# SaLFrostburn1_2.net
KiCad netlist of a schematic drawn in EAGLE
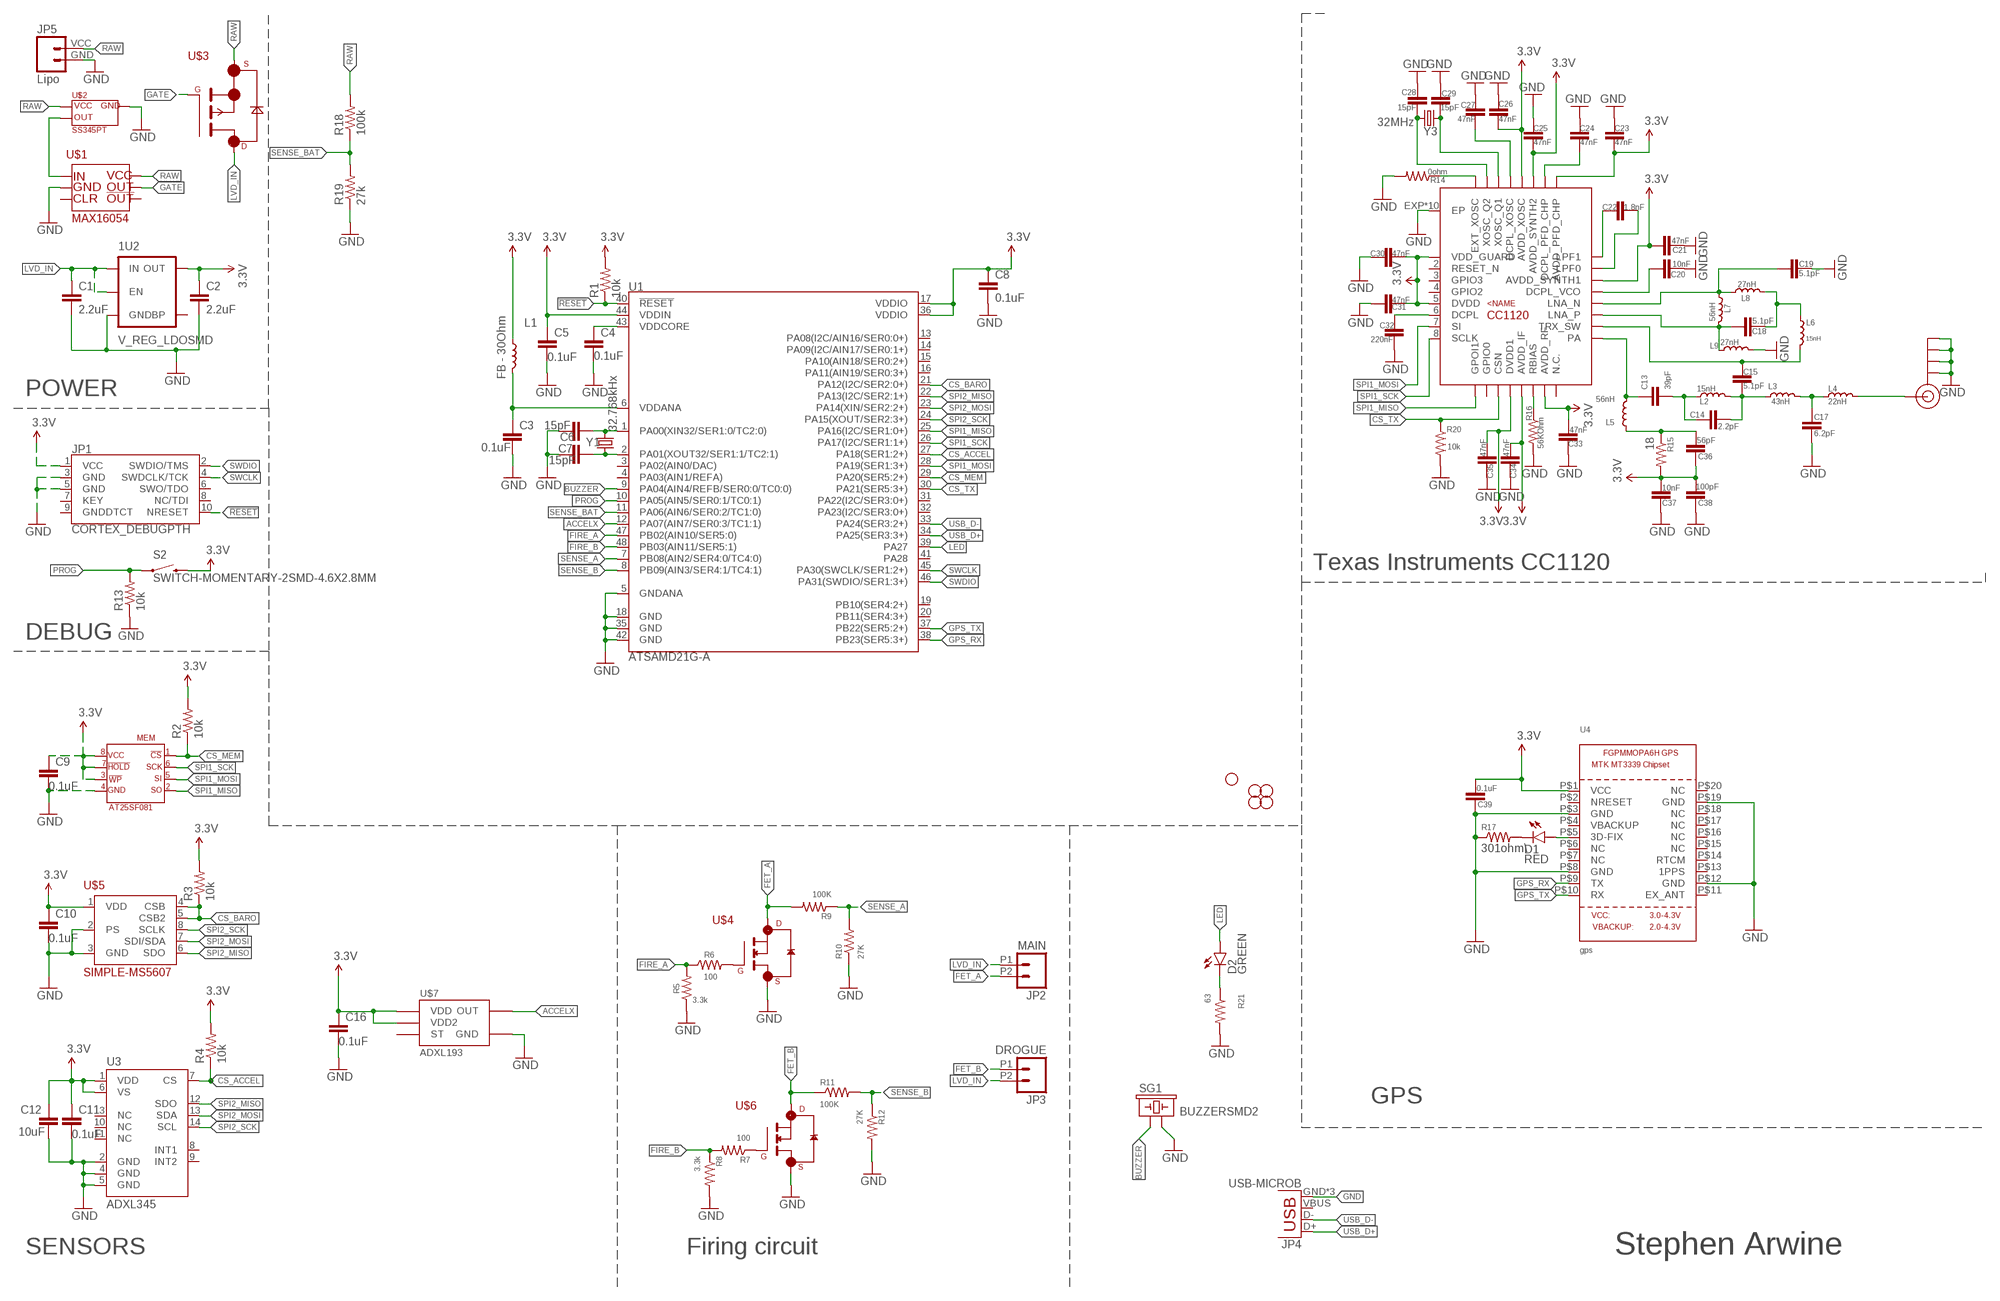
[diagram p0: schematic, sheet 1]

(export (version "E")
  (design (tool "Eeschema 10.0.6"))
  (components
    (comp (ref "1U2")
      (value "V_REG_LDOSMD")
      (footprint "eagle-import:SOT23-5")
      (libsource (lib "eagle-import") (part "V_REG_LDOSMD"))
    )
    (comp (ref "C1")
      (value "2.2uF")
      (footprint "eagle-import:0603-CAP")
      (libsource (lib "eagle-import") (part "CAP0603-CAP"))
    )
    (comp (ref "C2")
      (value "2.2uF")
      (footprint "eagle-import:0603-CAP")
      (libsource (lib "eagle-import") (part "CAP0603-CAP"))
    )
    (comp (ref "C3")
      (value "0.1uF")
      (footprint "eagle-import:0402-CAP")
      (libsource (lib "eagle-import") (part "SparkFun-Passives_CAP0402-CAP"))
    )
    (comp (ref "C4")
      (value "0.1uF")
      (footprint "eagle-import:0402-CAP")
      (libsource (lib "eagle-import") (part "SparkFun-Passives_CAP0402-CAP"))
    )
    (comp (ref "C5")
      (value "0.1uF")
      (footprint "eagle-import:0402-CAP")
      (libsource (lib "eagle-import") (part "SparkFun-Passives_CAP0402-CAP"))
    )
    (comp (ref "C6")
      (value "15pF")
      (footprint "eagle-import:0402-CAP")
      (libsource (lib "eagle-import") (part "SparkFun-Passives_CAP0402-CAP"))
    )
    (comp (ref "C7")
      (value "15pF")
      (footprint "eagle-import:0402-CAP")
      (libsource (lib "eagle-import") (part "SparkFun-Passives_CAP0402-CAP"))
    )
    (comp (ref "C8")
      (value "0.1uF")
      (footprint "eagle-import:0402-CAP")
      (libsource (lib "eagle-import") (part "SparkFun-Passives_CAP0402-CAP"))
    )
    (comp (ref "C9")
      (value "0.1uF")
      (footprint "eagle-import:0402-CAP")
      (libsource (lib "eagle-import") (part "SparkFun-Passives_CAP0402-CAP"))
    )
    (comp (ref "C10")
      (value "0.1uF")
      (footprint "eagle-import:0402-CAP")
      (libsource (lib "eagle-import") (part "SparkFun-Passives_CAP0402-CAP"))
    )
    (comp (ref "C11")
      (value "0.1uF")
      (footprint "eagle-import:0402-CAP")
      (libsource (lib "eagle-import") (part "SparkFun-Passives_CAP0402-CAP"))
    )
    (comp (ref "C12")
      (value "10uF")
      (footprint "eagle-import:0402-CAP")
      (libsource (lib "eagle-import") (part "SparkFun-Passives_CAP0402-CAP"))
    )
    (comp (ref "C13")
      (value "39pF")
      (footprint "eagle-import:0402-CAP")
      (libsource (lib "eagle-import") (part "CAP0402-CAP"))
    )
    (comp (ref "C14")
      (value "2.2pF")
      (footprint "eagle-import:0402-CAP")
      (libsource (lib "eagle-import") (part "CAP0402-CAP"))
    )
    (comp (ref "C15")
      (value "5.1pF")
      (footprint "eagle-import:0402-CAP")
      (libsource (lib "eagle-import") (part "CAP0402-CAP"))
    )
    (comp (ref "C16")
      (value "0.1uF")
      (footprint "eagle-import:0402-CAP")
      (libsource (lib "eagle-import") (part "SparkFun-Passives_CAP0402-CAP"))
    )
    (comp (ref "C17")
      (value "6.2pF")
      (footprint "eagle-import:0402-CAP")
      (libsource (lib "eagle-import") (part "CAP0402-CAP"))
    )
    (comp (ref "C18")
      (value "5.1pF")
      (footprint "eagle-import:0402-CAP")
      (libsource (lib "eagle-import") (part "CAP0402-CAP"))
    )
    (comp (ref "C19")
      (value "5.1pF")
      (footprint "eagle-import:0402-CAP")
      (libsource (lib "eagle-import") (part "CAP0402-CAP"))
    )
    (comp (ref "C20")
      (value "10nF")
      (footprint "eagle-import:0402-CAP")
      (libsource (lib "eagle-import") (part "CAP0402-CAP"))
    )
    (comp (ref "C21")
      (value "47nF")
      (footprint "eagle-import:0402-CAP")
      (libsource (lib "eagle-import") (part "CAP0402-CAP"))
    )
    (comp (ref "C22")
      (value "1.8nF")
      (footprint "eagle-import:0402-CAP")
      (libsource (lib "eagle-import") (part "CAP0402-CAP"))
    )
    (comp (ref "C23")
      (value "47nF")
      (footprint "eagle-import:0402-CAP")
      (libsource (lib "eagle-import") (part "CAP0402-CAP"))
    )
    (comp (ref "C24")
      (value "47nF")
      (footprint "eagle-import:0402-CAP")
      (libsource (lib "eagle-import") (part "CAP0402-CAP"))
    )
    (comp (ref "C25")
      (value "47nF")
      (footprint "eagle-import:0402-CAP")
      (libsource (lib "eagle-import") (part "CAP0402-CAP"))
    )
    (comp (ref "C26")
      (value "47nF")
      (footprint "eagle-import:0402-CAP")
      (libsource (lib "eagle-import") (part "CAP0402-CAP"))
    )
    (comp (ref "C27")
      (value "47nF")
      (footprint "eagle-import:0402-CAP")
      (libsource (lib "eagle-import") (part "CAP0402-CAP"))
    )
    (comp (ref "C28")
      (value "15pF")
      (footprint "eagle-import:0402-CAP")
      (libsource (lib "eagle-import") (part "CAP0402-CAP"))
    )
    (comp (ref "C29")
      (value "15pF")
      (footprint "eagle-import:0402-CAP")
      (libsource (lib "eagle-import") (part "CAP0402-CAP"))
    )
    (comp (ref "C30")
      (value "47nF")
      (footprint "eagle-import:0402-CAP")
      (libsource (lib "eagle-import") (part "CAP0402-CAP"))
    )
    (comp (ref "C31")
      (value "47nF")
      (footprint "eagle-import:0402-CAP")
      (libsource (lib "eagle-import") (part "CAP0402-CAP"))
    )
    (comp (ref "C32")
      (value "220nF")
      (footprint "eagle-import:0402-CAP")
      (libsource (lib "eagle-import") (part "CAP0402-CAP"))
    )
    (comp (ref "C33")
      (value "47nF")
      (footprint "eagle-import:0402-CAP")
      (libsource (lib "eagle-import") (part "CAP0402-CAP"))
    )
    (comp (ref "C34")
      (value "47nF")
      (footprint "eagle-import:0402-CAP")
      (libsource (lib "eagle-import") (part "CAP0402-CAP"))
    )
    (comp (ref "C35")
      (value "47nF")
      (footprint "eagle-import:0402-CAP")
      (libsource (lib "eagle-import") (part "CAP0402-CAP"))
    )
    (comp (ref "C36")
      (value "56pF")
      (footprint "eagle-import:0402-CAP")
      (libsource (lib "eagle-import") (part "CAP0402-CAP"))
    )
    (comp (ref "C37")
      (value "10nF")
      (footprint "eagle-import:0402-CAP")
      (libsource (lib "eagle-import") (part "CAP0402-CAP"))
    )
    (comp (ref "C38")
      (value "100pF")
      (footprint "eagle-import:0402-CAP")
      (libsource (lib "eagle-import") (part "CAP0402-CAP"))
    )
    (comp (ref "C39")
      (value "0.1uF")
      (footprint "eagle-import:0402-CAP")
      (libsource (lib "eagle-import") (part "CAP0402-CAP"))
    )
    (comp (ref "D1")
      (value "RED")
      (footprint "eagle-import:LED-0603")
      (libsource (lib "eagle-import") (part "LED-RED0603"))
    )
    (comp (ref "D2")
      (value "GREEN")
      (footprint "eagle-import:LED-1206")
      (libsource (lib "eagle-import") (part "LED-GREEN1206"))
    )
    (comp (ref "J$1")
      (value "SMA_EDGE")
      (footprint "eagle-import:SMA-EDGE")
      (libsource (lib "eagle-import") (part "SMA_EDGE"))
    )
    (comp (ref "JP1")
      (value "CORTEX_DEBUGPTH")
      (footprint "eagle-import:2X5-PTH-1.27MM")
      (libsource (lib "eagle-import") (part "CORTEX_DEBUGPTH"))
    )
    (comp (ref "JP2")
      (value "MAIN")
      (footprint "eagle-import:1X02_2.54_SCREWTERM")
      (libsource (lib "eagle-import") (part "M022.54MM_SCREWTERM"))
    )
    (comp (ref "JP3")
      (value "DROGUE")
      (footprint "eagle-import:1X02_2.54_SCREWTERM")
      (libsource (lib "eagle-import") (part "M022.54MM_SCREWTERM"))
    )
    (comp (ref "JP4")
      (value "USB-MICROB")
      (footprint "eagle-import:USB-MICROB")
      (libsource (lib "eagle-import") (part "USB-MICROB"))
    )
    (comp (ref "JP5")
      (value "Lipo")
      (footprint "eagle-import:JST-2-SMD-VERT")
      (libsource (lib "eagle-import") (part "M024UCON-15767"))
    )
    (comp (ref "L1")
      (value "FB - 30Ohm")
      (footprint "eagle-import:0603")
      (libsource (lib "eagle-import") (part "INDUCTOR0603"))
    )
    (comp (ref "L2")
      (value "15nH")
      (footprint "eagle-import:C0402")
      (libsource (lib "eagle-import") (part "INDUCTOR0402"))
    )
    (comp (ref "L3")
      (value "43nH")
      (footprint "eagle-import:C0402")
      (libsource (lib "eagle-import") (part "INDUCTOR0402"))
    )
    (comp (ref "L4")
      (value "22nH")
      (footprint "eagle-import:C0402")
      (libsource (lib "eagle-import") (part "INDUCTOR0402"))
    )
    (comp (ref "L5")
      (value "56nH")
      (footprint "eagle-import:C0402")
      (libsource (lib "eagle-import") (part "INDUCTOR0402"))
    )
    (comp (ref "L6")
      (value "15nH")
      (footprint "eagle-import:C0402")
      (libsource (lib "eagle-import") (part "INDUCTOR0402"))
    )
    (comp (ref "L7")
      (value "56nH")
      (footprint "eagle-import:C0402")
      (libsource (lib "eagle-import") (part "INDUCTOR0402"))
    )
    (comp (ref "L8")
      (value "27nH")
      (footprint "eagle-import:C0402")
      (libsource (lib "eagle-import") (part "INDUCTOR0402"))
    )
    (comp (ref "L9")
      (value "27nH")
      (footprint "eagle-import:C0402")
      (libsource (lib "eagle-import") (part "INDUCTOR0402"))
    )
    (comp (ref "MEM")
      (value "AT25SF081")
      (footprint "eagle-import:AT25SF081")
      (libsource (lib "eagle-import") (part "AT25SF081"))
    )
    (comp (ref "R1")
      (value "10k")
      (footprint "eagle-import:0402-RES")
      (libsource (lib "eagle-import") (part "RESISTOR0402-RES"))
    )
    (comp (ref "R2")
      (value "10k")
      (footprint "eagle-import:0402-RES")
      (libsource (lib "eagle-import") (part "RESISTOR0402-RES"))
    )
    (comp (ref "R3")
      (value "10k")
      (footprint "eagle-import:0402-RES")
      (libsource (lib "eagle-import") (part "RESISTOR0402-RES"))
    )
    (comp (ref "R4")
      (value "10k")
      (footprint "eagle-import:0402-RES")
      (libsource (lib "eagle-import") (part "RESISTOR0402-RES"))
    )
    (comp (ref "R5")
      (value "3.3k")
      (footprint "eagle-import:0402-RES")
      (libsource (lib "eagle-import") (part "RESISTOR0402"))
    )
    (comp (ref "R6")
      (value "100")
      (footprint "eagle-import:0402-RES")
      (libsource (lib "eagle-import") (part "RESISTOR0402"))
    )
    (comp (ref "R7")
      (value "100")
      (footprint "eagle-import:0402-RES")
      (libsource (lib "eagle-import") (part "RESISTOR0402"))
    )
    (comp (ref "R8")
      (value "3.3k")
      (footprint "eagle-import:0402-RES")
      (libsource (lib "eagle-import") (part "RESISTOR0402"))
    )
    (comp (ref "R9")
      (value "100K")
      (footprint "eagle-import:0402-RES")
      (libsource (lib "eagle-import") (part "RESISTOR0402"))
    )
    (comp (ref "R10")
      (value "27K")
      (footprint "eagle-import:0402-RES")
      (libsource (lib "eagle-import") (part "RESISTOR0402"))
    )
    (comp (ref "R11")
      (value "100K")
      (footprint "eagle-import:0402-RES")
      (libsource (lib "eagle-import") (part "RESISTOR0402"))
    )
    (comp (ref "R12")
      (value "27K")
      (footprint "eagle-import:0402-RES")
      (libsource (lib "eagle-import") (part "RESISTOR0402"))
    )
    (comp (ref "R13")
      (value "10k")
      (footprint "eagle-import:0402-RES")
      (libsource (lib "eagle-import") (part "RESISTOR0402-RES"))
    )
    (comp (ref "R14")
      (value "0ohm")
      (footprint "eagle-import:0402-RES")
      (libsource (lib "eagle-import") (part "RESISTOR0402-RES"))
    )
    (comp (ref "R15")
      (value "18")
      (footprint "eagle-import:0402-RES")
      (libsource (lib "eagle-import") (part "RESISTOR0402-RES"))
    )
    (comp (ref "R16")
      (value "56KOhm")
      (footprint "eagle-import:0402-RES")
      (libsource (lib "eagle-import") (part "RESISTOR0402-RES"))
    )
    (comp (ref "R17")
      (value "301ohm\\")
      (footprint "eagle-import:0402-RES")
      (libsource (lib "eagle-import") (part "RESISTOR0402-RES"))
    )
    (comp (ref "R18")
      (value "100k")
      (footprint "eagle-import:0402-RES")
      (libsource (lib "eagle-import") (part "RESISTOR0402-RES"))
    )
    (comp (ref "R19")
      (value "27k")
      (footprint "eagle-import:0402-RES")
      (libsource (lib "eagle-import") (part "RESISTOR0402-RES"))
    )
    (comp (ref "R20")
      (value "10k")
      (footprint "eagle-import:0402-RES")
      (libsource (lib "eagle-import") (part "RESISTOR0402-RES"))
    )
    (comp (ref "R21")
      (value "63")
      (footprint "eagle-import:0402-RES")
      (libsource (lib "eagle-import") (part "RESISTOR0402"))
    )
    (comp (ref "S2")
      (value "SWITCH-MOMENTARY-2SMD-4.6X2.8MM")
      (footprint "eagle-import:TACTILE_SWITCH_SMD_4.6X2.8MM")
      (libsource (lib "eagle-import") (part "SWITCH-MOMENTARY-2SMD-4.6X2.8MM"))
    )
    (comp (ref "SG1")
      (value "BUZZERSMD2")
      (footprint "eagle-import:BUZZER-CCV")
      (libsource (lib "eagle-import") (part "BUZZERSMD2"))
    )
    (comp (ref "STANDOFF1")
      (value "STAND-OFF")
      (footprint "eagle-import:STAND-OFF")
      (libsource (lib "eagle-import") (part "STAND-OFF"))
    )
    (comp (ref "STANDOFF2")
      (value "STAND-OFF")
      (footprint "eagle-import:STAND-OFF")
      (libsource (lib "eagle-import") (part "STAND-OFF"))
    )
    (comp (ref "STANDOFF3")
      (value "STAND-OFF")
      (footprint "eagle-import:STAND-OFF")
      (libsource (lib "eagle-import") (part "STAND-OFF"))
    )
    (comp (ref "STANDOFF4")
      (value "STAND-OFF")
      (footprint "eagle-import:STAND-OFF")
      (libsource (lib "eagle-import") (part "STAND-OFF"))
    )
    (comp (ref "STANDOFF5")
      (value "STAND-OFF")
      (footprint "eagle-import:STAND-OFF")
      (libsource (lib "eagle-import") (part "STAND-OFF"))
    )
    (comp (ref "TX/RX")
      (value "CC1120")
      (footprint "eagle-import:CC1120")
      (libsource (lib "eagle-import") (part "CC1120"))
    )
    (comp (ref "U$1")
      (value "MAX16054")
      (footprint "eagle-import:MAX16054")
      (libsource (lib "eagle-import") (part "MAX16054"))
    )
    (comp (ref "U$2")
      (value "SS345PT")
      (footprint "eagle-import:SS345PT")
      (libsource (lib "eagle-import") (part "SS345PT"))
    )
    (comp (ref "U$3")
      (value "SI7615ADN")
      (footprint "eagle-import:SI7615ADN")
      (libsource (lib "eagle-import") (part "SI7615ADN"))
    )
    (comp (ref "U$4")
      (value "SIS410DN")
      (footprint "eagle-import:POWERPACK1212-8")
      (libsource (lib "eagle-import") (part "SIS410DN"))
    )
    (comp (ref "U$5")
      (value "SIMPLE-MS5607")
      (footprint "eagle-import:MS5607")
      (libsource (lib "eagle-import") (part "SIMPLE-MS5607"))
    )
    (comp (ref "U$6")
      (value "SIS410DN")
      (footprint "eagle-import:POWERPACK1212-8")
      (libsource (lib "eagle-import") (part "SIS410DN"))
    )
    (comp (ref "U$7")
      (value "ADXL193")
      (footprint "eagle-import:ADXL193")
      (libsource (lib "eagle-import") (part "ADXL193"))
    )
    (comp (ref "U1")
      (value "ATSAMD21G-A")
      (footprint "eagle-import:TQFP-48")
      (libsource (lib "eagle-import") (part "ATSAMD21G-A"))
    )
    (comp (ref "U3")
      (value "ADXL345")
      (footprint "eagle-import:LGA14")
      (libsource (lib "eagle-import") (part "ADXL345"))
    )
    (comp (ref "U4")
      (value "gps")
      (footprint "eagle-import:FGPMMOPA6H")
      (libsource (lib "eagle-import") (part "GPS_FGPMMOPA6H"))
    )
    (comp (ref "Y1")
      (value "32.768kHx")
      (footprint "eagle-import:CRYSTAL-SMD-3.2X1.5MM")
      (libsource (lib "eagle-import") (part "CRYSTAL3.2X1.5MM"))
    )
    (comp (ref "Y3")
      (value "32MHz")
      (footprint "eagle-import:CRYSTAL-SMD-5X3")
      (libsource (lib "eagle-import") (part "CRYSTAL5X3"))
    )
  )
  (nets
    (net (code "1") (name "/~{RESET}") (class "Default")
      (node (ref "JP1") (pin "10") (pinfunction "NRESET_10") (pintype "bidirectional"))
      (node (ref "R1") (pin "1") (pinfunction "1_1") (pintype "passive"))
      (node (ref "U1") (pin "40") (pinfunction "~{RESET}_40") (pintype "bidirectional"))
    )
    (net (code "2") (name "3.3V") (class "Default")
      (node (ref "1U2") (pin "5") (pinfunction "OUT_5") (pintype "passive"))
      (node (ref "C10") (pin "1") (pinfunction "1_1") (pintype "passive"))
      (node (ref "C11") (pin "1") (pinfunction "1_1") (pintype "passive"))
      (node (ref "C12") (pin "1") (pinfunction "1_1") (pintype "passive"))
      (node (ref "C16") (pin "1") (pinfunction "1_1") (pintype "passive"))
      (node (ref "C2") (pin "1") (pinfunction "1_1") (pintype "passive"))
      (node (ref "C21") (pin "1") (pinfunction "1_1") (pintype "passive"))
      (node (ref "C23") (pin "2") (pinfunction "2_2") (pintype "passive"))
      (node (ref "C25") (pin "2") (pinfunction "2_2") (pintype "passive"))
      (node (ref "C26") (pin "2") (pinfunction "2_2") (pintype "passive"))
      (node (ref "C30") (pin "2") (pinfunction "2_2") (pintype "passive"))
      (node (ref "C31") (pin "2") (pinfunction "2_2") (pintype "passive"))
      (node (ref "C33") (pin "2") (pinfunction "2_2") (pintype "passive"))
      (node (ref "C34") (pin "2") (pinfunction "2_2") (pintype "passive"))
      (node (ref "C35") (pin "2") (pinfunction "2_2") (pintype "passive"))
      (node (ref "C36") (pin "1") (pinfunction "1_1") (pintype "passive"))
      (node (ref "C37") (pin "2") (pinfunction "2_2") (pintype "passive"))
      (node (ref "C38") (pin "2") (pinfunction "2_2") (pintype "passive"))
      (node (ref "C39") (pin "2") (pinfunction "2_2") (pintype "passive"))
      (node (ref "C5") (pin "1") (pinfunction "1_1") (pintype "passive"))
      (node (ref "C8") (pin "1") (pinfunction "1_1") (pintype "passive"))
      (node (ref "C9") (pin "1") (pinfunction "1_1") (pintype "passive"))
      (node (ref "JP1") (pin "1") (pinfunction "VCC_1") (pintype "bidirectional"))
      (node (ref "L1") (pin "1") (pinfunction "1_1") (pintype "passive"))
      (node (ref "MEM") (pin "!HOLD") (pinfunction "~{HOLD}_!HOLD") (pintype "bidirectional"))
      (node (ref "MEM") (pin "!WP") (pinfunction "~{WP}_!WP") (pintype "bidirectional"))
      (node (ref "MEM") (pin "VCC") (pinfunction "VCC_VCC") (pintype "bidirectional"))
      (node (ref "R1") (pin "2") (pinfunction "2_2") (pintype "passive"))
      (node (ref "R15") (pin "2") (pinfunction "2_2") (pintype "passive"))
      (node (ref "R2") (pin "2") (pinfunction "2_2") (pintype "passive"))
      (node (ref "R3") (pin "2") (pinfunction "2_2") (pintype "passive"))
      (node (ref "R4") (pin "2") (pinfunction "2_2") (pintype "passive"))
      (node (ref "S2") (pin "3") (pinfunction "2_3") (pintype "passive"))
      (node (ref "S2") (pin "4") (pinfunction "2_4") (pintype "passive"))
      (node (ref "TX/RX") (pin "1") (pinfunction "VDD_GUARD_1") (pintype "bidirectional"))
      (node (ref "TX/RX") (pin "12") (pinfunction "DVDD1_12") (pintype "bidirectional"))
      (node (ref "TX/RX") (pin "13") (pinfunction "AVDD_IF_13") (pintype "bidirectional"))
      (node (ref "TX/RX") (pin "15") (pinfunction "AVDD_RF_15") (pintype "bidirectional"))
      (node (ref "TX/RX") (pin "22") (pinfunction "AVDD_SYNTH1_22") (pintype "bidirectional"))
      (node (ref "TX/RX") (pin "25") (pinfunction "AVDD_PFD_CHP_25") (pintype "bidirectional"))
      (node (ref "TX/RX") (pin "27") (pinfunction "AVDD_SYNTH2_27") (pintype "bidirectional"))
      (node (ref "TX/RX") (pin "28") (pinfunction "AVDD_XOSC_28") (pintype "bidirectional"))
      (node (ref "TX/RX") (pin "5") (pinfunction "DVDD_5") (pintype "bidirectional"))
      (node (ref "U$5") (pin "1") (pinfunction "VDD_1") (pintype "bidirectional"))
      (node (ref "U$7") (pin "P$7") (pinfunction "VDD_P$7") (pintype "bidirectional"))
      (node (ref "U$7") (pin "P$8") (pinfunction "VDD2_P$8") (pintype "bidirectional"))
      (node (ref "U1") (pin "17") (pinfunction "VDDIO_17") (pintype "bidirectional"))
      (node (ref "U1") (pin "36") (pinfunction "VDDIO_36") (pintype "bidirectional"))
      (node (ref "U1") (pin "44") (pinfunction "VDDIN_44") (pintype "bidirectional"))
      (node (ref "U3") (pin "1") (pinfunction "VDD_1") (pintype "bidirectional"))
      (node (ref "U3") (pin "6") (pinfunction "VS_6") (pintype "bidirectional"))
      (node (ref "U4") (pin "P$1") (pinfunction "VCC_P$1") (pintype "bidirectional"))
    )
    (net (code "3") (name "ACCELX") (class "Default")
      (node (ref "U$7") (pin "P$6") (pinfunction "OUT_P$6") (pintype "bidirectional"))
      (node (ref "U1") (pin "12") (pinfunction "PA07(AIN7/SER0:3/TC1:1)_12") (pintype "bidirectional"))
    )
    (net (code "4") (name "BUZZER") (class "Default")
      (node (ref "SG1") (pin "+") (pinfunction "1_+") (pintype "passive"))
      (node (ref "U1") (pin "9") (pinfunction "PA04(AIN4/REFB/SER0:0/TC0:0)_9") (pintype "bidirectional"))
    )
    (net (code "5") (name "CS_ACCEL") (class "Default")
      (node (ref "R4") (pin "1") (pinfunction "1_1") (pintype "passive"))
      (node (ref "U1") (pin "27") (pinfunction "PA18(SER1:2+)_27") (pintype "bidirectional"))
      (node (ref "U3") (pin "7") (pinfunction "CS_7") (pintype "bidirectional"))
    )
    (net (code "6") (name "CS_BARO") (class "Default")
      (node (ref "R3") (pin "1") (pinfunction "1_1") (pintype "passive"))
      (node (ref "U$5") (pin "4") (pinfunction "CSB_4") (pintype "bidirectional"))
      (node (ref "U$5") (pin "5") (pinfunction "CSB2_5") (pintype "bidirectional"))
      (node (ref "U1") (pin "21") (pinfunction "PA12(I2C/SER2:0+)_21") (pintype "bidirectional"))
    )
    (net (code "7") (name "CS_MEM") (class "Default")
      (node (ref "MEM") (pin "!CS") (pinfunction "~{CS}_!CS") (pintype "bidirectional"))
      (node (ref "R2") (pin "1") (pinfunction "1_1") (pintype "passive"))
      (node (ref "U1") (pin "29") (pinfunction "PA20(SER5:2+)_29") (pintype "bidirectional"))
    )
    (net (code "8") (name "CS_TX") (class "Default")
      (node (ref "R20") (pin "1") (pinfunction "1_1") (pintype "passive"))
      (node (ref "TX/RX") (pin "11") (pinfunction "CSN_11") (pintype "bidirectional"))
      (node (ref "U1") (pin "30") (pinfunction "PA21(SER5:3+)_30") (pintype "bidirectional"))
    )
    (net (code "9") (name "FET_A") (class "Default")
      (node (ref "JP2") (pin "P2") (pinfunction "2_P2") (pintype "passive"))
      (node (ref "R9") (pin "2") (pinfunction "2_2") (pintype "passive"))
      (node (ref "U$4") (pin "5") (pinfunction "D_5") (pintype "bidirectional"))
      (node (ref "U$4") (pin "6") (pinfunction "D_6") (pintype "bidirectional"))
      (node (ref "U$4") (pin "7") (pinfunction "D_7") (pintype "bidirectional"))
      (node (ref "U$4") (pin "8") (pinfunction "D_8") (pintype "bidirectional"))
    )
    (net (code "10") (name "FET_B") (class "Default")
      (node (ref "JP3") (pin "P1") (pinfunction "1_P1") (pintype "passive"))
      (node (ref "R11") (pin "1") (pinfunction "1_1") (pintype "passive"))
      (node (ref "U$6") (pin "5") (pinfunction "D_5") (pintype "bidirectional"))
      (node (ref "U$6") (pin "6") (pinfunction "D_6") (pintype "bidirectional"))
      (node (ref "U$6") (pin "7") (pinfunction "D_7") (pintype "bidirectional"))
      (node (ref "U$6") (pin "8") (pinfunction "D_8") (pintype "bidirectional"))
    )
    (net (code "11") (name "FIRE_A") (class "Default")
      (node (ref "R5") (pin "2") (pinfunction "2_2") (pintype "passive"))
      (node (ref "R6") (pin "1") (pinfunction "1_1") (pintype "passive"))
      (node (ref "U1") (pin "47") (pinfunction "PB02(AIN10/SER5:0)_47") (pintype "bidirectional"))
    )
    (net (code "12") (name "FIRE_B") (class "Default")
      (node (ref "R7") (pin "2") (pinfunction "2_2") (pintype "passive"))
      (node (ref "R8") (pin "1") (pinfunction "1_1") (pintype "passive"))
      (node (ref "U1") (pin "48") (pinfunction "PB03(AIN11/SER5:1)_48") (pintype "bidirectional"))
    )
    (net (code "13") (name "GATE") (class "Default")
      (node (ref "U$1") (pin "OUT") (pinfunction "OUT_OUT") (pintype "bidirectional"))
      (node (ref "U$3") (pin "G") (pinfunction "G_G") (pintype "bidirectional"))
    )
    (net (code "14") (name "GND") (class "Default")
      (node (ref "1U2") (pin "2") (pinfunction "GND_2") (pintype "input"))
      (node (ref "C1") (pin "2") (pinfunction "2_2") (pintype "passive"))
      (node (ref "C10") (pin "2") (pinfunction "2_2") (pintype "passive"))
      (node (ref "C11") (pin "2") (pinfunction "2_2") (pintype "passive"))
      (node (ref "C12") (pin "2") (pinfunction "2_2") (pintype "passive"))
      (node (ref "C16") (pin "2") (pinfunction "2_2") (pintype "passive"))
      (node (ref "C17") (pin "2") (pinfunction "2_2") (pintype "passive"))
      (node (ref "C19") (pin "2") (pinfunction "2_2") (pintype "passive"))
      (node (ref "C2") (pin "2") (pinfunction "2_2") (pintype "passive"))
      (node (ref "C20") (pin "2") (pinfunction "2_2") (pintype "passive"))
      (node (ref "C21") (pin "2") (pinfunction "2_2") (pintype "passive"))
      (node (ref "C23") (pin "1") (pinfunction "1_1") (pintype "passive"))
      (node (ref "C24") (pin "1") (pinfunction "1_1") (pintype "passive"))
      (node (ref "C25") (pin "1") (pinfunction "1_1") (pintype "passive"))
      (node (ref "C26") (pin "1") (pinfunction "1_1") (pintype "passive"))
      (node (ref "C27") (pin "1") (pinfunction "1_1") (pintype "passive"))
      (node (ref "C28") (pin "1") (pinfunction "1_1") (pintype "passive"))
      (node (ref "C29") (pin "1") (pinfunction "1_1") (pintype "passive"))
      (node (ref "C3") (pin "2") (pinfunction "2_2") (pintype "passive"))
      (node (ref "C30") (pin "1") (pinfunction "1_1") (pintype "passive"))
      (node (ref "C31") (pin "1") (pinfunction "1_1") (pintype "passive"))
      (node (ref "C32") (pin "1") (pinfunction "1_1") (pintype "passive"))
      (node (ref "C33") (pin "1") (pinfunction "1_1") (pintype "passive"))
      (node (ref "C34") (pin "1") (pinfunction "1_1") (pintype "passive"))
      (node (ref "C35") (pin "1") (pinfunction "1_1") (pintype "passive"))
      (node (ref "C37") (pin "1") (pinfunction "1_1") (pintype "passive"))
      (node (ref "C38") (pin "1") (pinfunction "1_1") (pintype "passive"))
      (node (ref "C39") (pin "1") (pinfunction "1_1") (pintype "passive"))
      (node (ref "C4") (pin "2") (pinfunction "2_2") (pintype "passive"))
      (node (ref "C5") (pin "2") (pinfunction "2_2") (pintype "passive"))
      (node (ref "C6") (pin "2") (pinfunction "2_2") (pintype "passive"))
      (node (ref "C7") (pin "2") (pinfunction "2_2") (pintype "passive"))
      (node (ref "C8") (pin "2") (pinfunction "2_2") (pintype "passive"))
      (node (ref "C9") (pin "2") (pinfunction "2_2") (pintype "passive"))
      (node (ref "J$1") (pin "GND@0") (pinfunction "GND_GND@0") (pintype "bidirectional"))
      (node (ref "J$1") (pin "GND@1") (pinfunction "GND_GND@1") (pintype "bidirectional"))
      (node (ref "J$1") (pin "GND@2") (pinfunction "GND_GND@2") (pintype "bidirectional"))
      (node (ref "J$1") (pin "GND@3") (pinfunction "GND_GND@3") (pintype "bidirectional"))
      (node (ref "JP1") (pin "3") (pinfunction "GND_3") (pintype "bidirectional"))
      (node (ref "JP1") (pin "5") (pinfunction "GND_5") (pintype "bidirectional"))
      (node (ref "JP4") (pin "GND") (pinfunction "GND_GND") (pintype "bidirectional"))
      (node (ref "JP4") (pin "MT1") (pinfunction "GND_MT1") (pintype "bidirectional"))
      (node (ref "JP4") (pin "MT2") (pinfunction "GND_MT2") (pintype "bidirectional"))
      (node (ref "JP5") (pin "GND") (pinfunction "1_GND") (pintype "passive"))
      (node (ref "L9") (pin "2") (pinfunction "2_2") (pintype "passive"))
      (node (ref "MEM") (pin "GND") (pinfunction "GND_GND") (pintype "bidirectional"))
      (node (ref "R10") (pin "1") (pinfunction "1_1") (pintype "passive"))
      (node (ref "R12") (pin "2") (pinfunction "2_2") (pintype "passive"))
      (node (ref "R13") (pin "1") (pinfunction "1_1") (pintype "passive"))
      (node (ref "R14") (pin "2") (pinfunction "2_2") (pintype "passive"))
      (node (ref "R16") (pin "2") (pinfunction "2_2") (pintype "passive"))
      (node (ref "R17") (pin "1") (pinfunction "1_1") (pintype "passive"))
      (node (ref "R19") (pin "1") (pinfunction "1_1") (pintype "passive"))
      (node (ref "R20") (pin "2") (pinfunction "2_2") (pintype "passive"))
      (node (ref "R21") (pin "2") (pinfunction "2_2") (pintype "passive"))
      (node (ref "R5") (pin "1") (pinfunction "1_1") (pintype "passive"))
      (node (ref "R8") (pin "2") (pinfunction "2_2") (pintype "passive"))
      (node (ref "SG1") (pin "-") (pinfunction "2_-") (pintype "passive"))
      (node (ref "TX/RX") (pin "EXP") (pinfunction "EP_EXP") (pintype "bidirectional"))
      (node (ref "TX/RX") (pin "EXP@1") (pinfunction "EP_EXP@1") (pintype "bidirectional"))
      (node (ref "TX/RX") (pin "EXP@2") (pinfunction "EP_EXP@2") (pintype "bidirectional"))
      (node (ref "TX/RX") (pin "EXP@3") (pinfunction "EP_EXP@3") (pintype "bidirectional"))
      (node (ref "TX/RX") (pin "EXP@4") (pinfunction "EP_EXP@4") (pintype "bidirectional"))
      (node (ref "TX/RX") (pin "EXP@5") (pinfunction "EP_EXP@5") (pintype "bidirectional"))
      (node (ref "TX/RX") (pin "EXP@6") (pinfunction "EP_EXP@6") (pintype "bidirectional"))
      (node (ref "TX/RX") (pin "EXP@7") (pinfunction "EP_EXP@7") (pintype "bidirectional"))
      (node (ref "TX/RX") (pin "EXP@8") (pinfunction "EP_EXP@8") (pintype "bidirectional"))
      (node (ref "TX/RX") (pin "EXP@9") (pinfunction "EP_EXP@9") (pintype "bidirectional"))
      (node (ref "U$1") (pin "GND") (pinfunction "GND_GND") (pintype "bidirectional"))
      (node (ref "U$2") (pin "GND") (pinfunction "GND_GND") (pintype "bidirectional"))
      (node (ref "U$4") (pin "1") (pinfunction "S_1") (pintype "bidirectional"))
      (node (ref "U$4") (pin "2") (pinfunction "S_2") (pintype "bidirectional"))
      (node (ref "U$4") (pin "3") (pinfunction "S_3") (pintype "bidirectional"))
      (node (ref "U$5") (pin "2") (pinfunction "PS_2") (pintype "bidirectional"))
      (node (ref "U$5") (pin "3") (pinfunction "GND_3") (pintype "bidirectional"))
      (node (ref "U$6") (pin "1") (pinfunction "S_1") (pintype "bidirectional"))
      (node (ref "U$6") (pin "2") (pinfunction "S_2") (pintype "bidirectional"))
      (node (ref "U$6") (pin "3") (pinfunction "S_3") (pintype "bidirectional"))
      (node (ref "U$7") (pin "P$3") (pinfunction "GND_P$3") (pintype "bidirectional"))
      (node (ref "U1") (pin "18") (pinfunction "GND_18") (pintype "bidirectional"))
      (node (ref "U1") (pin "35") (pinfunction "GND_35") (pintype "bidirectional"))
      (node (ref "U1") (pin "42") (pinfunction "GND_42") (pintype "bidirectional"))
      (node (ref "U1") (pin "5") (pinfunction "GNDANA_5") (pintype "bidirectional"))
      (node (ref "U3") (pin "2") (pinfunction "GND_2") (pintype "bidirectional"))
      (node (ref "U3") (pin "4") (pinfunction "GND_4") (pintype "bidirectional"))
      (node (ref "U3") (pin "5") (pinfunction "GND_5") (pintype "bidirectional"))
      (node (ref "U4") (pin "P$12") (pinfunction "GND_P$12") (pintype "bidirectional"))
      (node (ref "U4") (pin "P$19") (pinfunction "GND_P$19") (pintype "bidirectional"))
      (node (ref "U4") (pin "P$3") (pinfunction "GND_P$3") (pintype "bidirectional"))
      (node (ref "U4") (pin "P$8") (pinfunction "GND_P$8") (pintype "bidirectional"))
    )
    (net (code "15") (name "GPS_RX") (class "Default")
      (node (ref "U1") (pin "38") (pinfunction "PB23(SER5:3+)_38") (pintype "bidirectional"))
      (node (ref "U4") (pin "P$9") (pinfunction "TX_P$9") (pintype "bidirectional"))
    )
    (net (code "16") (name "GPS_TX") (class "Default")
      (node (ref "U1") (pin "37") (pinfunction "PB22(SER5:2+)_37") (pintype "bidirectional"))
      (node (ref "U4") (pin "P$10") (pinfunction "RX_P$10") (pintype "bidirectional"))
    )
    (net (code "17") (name "LED") (class "Default")
      (node (ref "D2") (pin "A") (pinfunction "A_A") (pintype "passive"))
      (node (ref "U1") (pin "39") (pinfunction "PA27_39") (pintype "bidirectional"))
    )
    (net (code "18") (name "LVD_IN") (class "Default")
      (node (ref "1U2") (pin "1") (pinfunction "IN_1") (pintype "input"))
      (node (ref "1U2") (pin "3") (pinfunction "EN_3") (pintype "input"))
      (node (ref "C1") (pin "1") (pinfunction "1_1") (pintype "passive"))
      (node (ref "JP2") (pin "P1") (pinfunction "1_P1") (pintype "passive"))
      (node (ref "JP3") (pin "P2") (pinfunction "2_P2") (pintype "passive"))
      (node (ref "U$3") (pin "D1") (pinfunction "D_D1") (pintype "bidirectional"))
      (node (ref "U$3") (pin "D2") (pinfunction "D_D2") (pintype "bidirectional"))
      (node (ref "U$3") (pin "D3") (pinfunction "D_D3") (pintype "bidirectional"))
      (node (ref "U$3") (pin "D4") (pinfunction "D_D4") (pintype "bidirectional"))
    )
    (net (code "19") (name "Net-(C13-Pad2)") (class "Default")
      (node (ref "C13") (pin "2") (pinfunction "2_2") (pintype "passive"))
      (node (ref "C14") (pin "1") (pinfunction "1_1") (pintype "passive"))
      (node (ref "L2") (pin "1") (pinfunction "1_1") (pintype "passive"))
    )
    (net (code "20") (name "Net-(C14-Pad2)") (class "Default")
      (node (ref "C14") (pin "2") (pinfunction "2_2") (pintype "passive"))
      (node (ref "C15") (pin "1") (pinfunction "1_1") (pintype "passive"))
      (node (ref "L2") (pin "2") (pinfunction "2_2") (pintype "passive"))
      (node (ref "L3") (pin "1") (pinfunction "1_1") (pintype "passive"))
    )
    (net (code "21") (name "Net-(C17-Pad1)") (class "Default")
      (node (ref "C17") (pin "1") (pinfunction "1_1") (pintype "passive"))
      (node (ref "L3") (pin "2") (pinfunction "2_2") (pintype "passive"))
      (node (ref "L4") (pin "1") (pinfunction "1_1") (pintype "passive"))
    )
    (net (code "22") (name "Net-(C18-Pad2)") (class "Default")
      (node (ref "C18") (pin "2") (pinfunction "2_2") (pintype "passive"))
      (node (ref "L6") (pin "1") (pinfunction "1_1") (pintype "passive"))
      (node (ref "L8") (pin "2") (pinfunction "2_2") (pintype "passive"))
    )
    (net (code "23") (name "Net-(C36-Pad2)") (class "Default")
      (node (ref "C36") (pin "2") (pinfunction "2_2") (pintype "passive"))
      (node (ref "L5") (pin "1") (pinfunction "1_1") (pintype "passive"))
      (node (ref "R15") (pin "1") (pinfunction "1_1") (pintype "passive"))
    )
    (net (code "24") (name "Net-(D1-PadC)") (class "Default")
      (node (ref "D1") (pin "C") (pinfunction "C_C") (pintype "passive"))
      (node (ref "R17") (pin "2") (pinfunction "2_2") (pintype "passive"))
    )
    (net (code "25") (name "Net-(D2-PadC)") (class "Default")
      (node (ref "D2") (pin "C") (pinfunction "C_C") (pintype "passive"))
      (node (ref "R21") (pin "1") (pinfunction "1_1") (pintype "passive"))
    )
    (net (code "26") (name "Net-(J$1-SIGNAL)") (class "Default")
      (node (ref "J$1") (pin "SIG") (pinfunction "SIGNAL_SIG") (pintype "bidirectional"))
      (node (ref "L4") (pin "2") (pinfunction "2_2") (pintype "passive"))
    )
    (net (code "27") (name "Net-(TX/RX-DCPL)") (class "Default")
      (node (ref "C32") (pin "2") (pinfunction "2_2") (pintype "passive"))
      (node (ref "TX/RX") (pin "6") (pinfunction "DCPL_6") (pintype "bidirectional"))
    )
    (net (code "28") (name "Net-(TX/RX-DCPL_PFD_CHP)") (class "Default")
      (node (ref "C24") (pin "2") (pinfunction "2_2") (pintype "passive"))
      (node (ref "TX/RX") (pin "26") (pinfunction "DCPL_PFD_CHP_26") (pintype "bidirectional"))
    )
    (net (code "29") (name "Net-(TX/RX-DCPL_VCO)") (class "Default")
      (node (ref "C20") (pin "1") (pinfunction "1_1") (pintype "passive"))
      (node (ref "TX/RX") (pin "21") (pinfunction "DCPL_VCO_21") (pintype "bidirectional"))
    )
    (net (code "30") (name "Net-(TX/RX-DCPL_XOSC)") (class "Default")
      (node (ref "C27") (pin "2") (pinfunction "2_2") (pintype "passive"))
      (node (ref "TX/RX") (pin "29") (pinfunction "DCPL_XOSC_29") (pintype "bidirectional"))
    )
    (net (code "31") (name "Net-(TX/RX-EXT_XOSC)") (class "Default")
      (node (ref "R14") (pin "1") (pinfunction "1_1") (pintype "passive"))
      (node (ref "TX/RX") (pin "32") (pinfunction "EXT_XOSC_32") (pintype "bidirectional"))
    )
    (net (code "32") (name "Net-(TX/RX-LNA_N)") (class "Default")
      (node (ref "C19") (pin "1") (pinfunction "1_1") (pintype "passive"))
      (node (ref "L7") (pin "1") (pinfunction "1_1") (pintype "passive"))
      (node (ref "L8") (pin "1") (pinfunction "1_1") (pintype "passive"))
      (node (ref "TX/RX") (pin "20") (pinfunction "LNA_N_20") (pintype "bidirectional"))
    )
    (net (code "33") (name "Net-(TX/RX-LNA_P)") (class "Default")
      (node (ref "C18") (pin "1") (pinfunction "1_1") (pintype "passive"))
      (node (ref "L7") (pin "2") (pinfunction "2_2") (pintype "passive"))
      (node (ref "L9") (pin "1") (pinfunction "1_1") (pintype "passive"))
      (node (ref "TX/RX") (pin "19") (pinfunction "LNA_P_19") (pintype "bidirectional"))
    )
    (net (code "34") (name "Net-(TX/RX-LPF0)") (class "Default")
      (node (ref "C22") (pin "2") (pinfunction "2_2") (pintype "passive"))
      (node (ref "TX/RX") (pin "23") (pinfunction "LPF0_23") (pintype "bidirectional"))
    )
    (net (code "35") (name "Net-(TX/RX-LPF1)") (class "Default")
      (node (ref "C22") (pin "1") (pinfunction "1_1") (pintype "passive"))
      (node (ref "TX/RX") (pin "24") (pinfunction "LPF1_24") (pintype "bidirectional"))
    )
    (net (code "36") (name "Net-(TX/RX-PA)") (class "Default")
      (node (ref "C13") (pin "1") (pinfunction "1_1") (pintype "passive"))
      (node (ref "L5") (pin "2") (pinfunction "2_2") (pintype "passive"))
      (node (ref "TX/RX") (pin "17") (pinfunction "PA_17") (pintype "bidirectional"))
    )
    (net (code "37") (name "Net-(TX/RX-RBIAS)") (class "Default")
      (node (ref "R16") (pin "1") (pinfunction "1_1") (pintype "passive"))
      (node (ref "TX/RX") (pin "14") (pinfunction "RBIAS_14") (pintype "bidirectional"))
    )
    (net (code "38") (name "Net-(TX/RX-TRX_SW)") (class "Default")
      (node (ref "C15") (pin "2") (pinfunction "2_2") (pintype "passive"))
      (node (ref "L6") (pin "2") (pinfunction "2_2") (pintype "passive"))
      (node (ref "TX/RX") (pin "18") (pinfunction "TRX_SW_18") (pintype "bidirectional"))
    )
    (net (code "39") (name "Net-(TX/RX-XOSC_Q1)") (class "Default")
      (node (ref "C29") (pin "2") (pinfunction "2_2") (pintype "passive"))
      (node (ref "TX/RX") (pin "30") (pinfunction "XOSC_Q1_30") (pintype "bidirectional"))
      (node (ref "Y3") (pin "3") (pinfunction "2_3") (pintype "passive"))
    )
    (net (code "40") (name "Net-(TX/RX-XOSC_Q2)") (class "Default")
      (node (ref "C28") (pin "2") (pinfunction "2_2") (pintype "passive"))
      (node (ref "TX/RX") (pin "31") (pinfunction "XOSC_Q2_31") (pintype "bidirectional"))
      (node (ref "Y3") (pin "1") (pinfunction "1_1") (pintype "passive"))
    )
    (net (code "41") (name "Net-(U$1-PadIN)") (class "Default")
      (node (ref "U$1") (pin "IN") (pinfunction "IN_IN") (pintype "bidirectional"))
      (node (ref "U$2") (pin "OUT") (pinfunction "OUT_OUT") (pintype "bidirectional"))
    )
    (net (code "42") (name "Net-(U$4-G)") (class "Default")
      (node (ref "R6") (pin "2") (pinfunction "2_2") (pintype "passive"))
      (node (ref "U$4") (pin "4") (pinfunction "G_4") (pintype "bidirectional"))
    )
    (net (code "43") (name "Net-(U$6-G)") (class "Default")
      (node (ref "R7") (pin "1") (pinfunction "1_1") (pintype "passive"))
      (node (ref "U$6") (pin "4") (pinfunction "G_4") (pintype "bidirectional"))
    )
    (net (code "44") (name "Net-(U1-PA00(XIN32{slash}SER1:0{slash}TC2:0))") (class "Default")
      (node (ref "C6") (pin "1") (pinfunction "1_1") (pintype "passive"))
      (node (ref "U1") (pin "1") (pinfunction "PA00(XIN32/SER1:0/TC2:0)_1") (pintype "bidirectional"))
      (node (ref "Y1") (pin "P$2") (pinfunction "2_P$2") (pintype "passive"))
    )
    (net (code "45") (name "Net-(U1-PA01(XOUT32{slash}SER1:1{slash}TC2:1))") (class "Default")
      (node (ref "C7") (pin "1") (pinfunction "1_1") (pintype "passive"))
      (node (ref "U1") (pin "2") (pinfunction "PA01(XOUT32/SER1:1/TC2:1)_2") (pintype "bidirectional"))
      (node (ref "Y1") (pin "P$1") (pinfunction "1_P$1") (pintype "passive"))
    )
    (net (code "46") (name "Net-(U1-VDDANA)") (class "Default")
      (node (ref "C3") (pin "1") (pinfunction "1_1") (pintype "passive"))
      (node (ref "L1") (pin "2") (pinfunction "2_2") (pintype "passive"))
      (node (ref "U1") (pin "6") (pinfunction "VDDANA_6") (pintype "bidirectional"))
    )
    (net (code "47") (name "Net-(U1-VDDCORE)") (class "Default")
      (node (ref "C4") (pin "1") (pinfunction "1_1") (pintype "passive"))
      (node (ref "U1") (pin "43") (pinfunction "VDDCORE_43") (pintype "bidirectional"))
    )
    (net (code "48") (name "Net-(U4-3D-FIX)") (class "Default")
      (node (ref "D1") (pin "A") (pinfunction "A_A") (pintype "passive"))
      (node (ref "U4") (pin "P$5") (pinfunction "3D-FIX_P$5") (pintype "bidirectional"))
    )
    (net (code "49") (name "PROG") (class "Default")
      (node (ref "R13") (pin "2") (pinfunction "2_2") (pintype "passive"))
      (node (ref "S2") (pin "1") (pinfunction "1_1") (pintype "passive"))
      (node (ref "S2") (pin "2") (pinfunction "1_2") (pintype "passive"))
      (node (ref "U1") (pin "10") (pinfunction "PA05(AIN5/SER0:1/TC0:1)_10") (pintype "bidirectional"))
    )
    (net (code "50") (name "RAW") (class "Default")
      (node (ref "JP5") (pin "VCC") (pinfunction "2_VCC") (pintype "passive"))
      (node (ref "R18") (pin "2") (pinfunction "2_2") (pintype "passive"))
      (node (ref "U$1") (pin "VCC") (pinfunction "VCC_VCC") (pintype "bidirectional"))
      (node (ref "U$2") (pin "VCC") (pinfunction "VCC_VCC") (pintype "bidirectional"))
      (node (ref "U$3") (pin "S1") (pinfunction "S_S1") (pintype "bidirectional"))
      (node (ref "U$3") (pin "S2") (pinfunction "S_S2") (pintype "bidirectional"))
      (node (ref "U$3") (pin "S3") (pinfunction "S_S3") (pintype "bidirectional"))
    )
    (net (code "51") (name "SENSE_A") (class "Default")
      (node (ref "R10") (pin "2") (pinfunction "2_2") (pintype "passive"))
      (node (ref "R9") (pin "1") (pinfunction "1_1") (pintype "passive"))
      (node (ref "U1") (pin "7") (pinfunction "PB08(AIN2/SER4:0/TC4:0)_7") (pintype "bidirectional"))
    )
    (net (code "52") (name "SENSE_B") (class "Default")
      (node (ref "R11") (pin "2") (pinfunction "2_2") (pintype "passive"))
      (node (ref "R12") (pin "1") (pinfunction "1_1") (pintype "passive"))
      (node (ref "U1") (pin "8") (pinfunction "PB09(AIN3/SER4:1/TC4:1)_8") (pintype "bidirectional"))
    )
    (net (code "53") (name "SENSE_BAT") (class "Default")
      (node (ref "R18") (pin "1") (pinfunction "1_1") (pintype "passive"))
      (node (ref "R19") (pin "2") (pinfunction "2_2") (pintype "passive"))
      (node (ref "U1") (pin "11") (pinfunction "PA06(AIN6/SER0:2/TC1:0)_11") (pintype "bidirectional"))
    )
    (net (code "54") (name "SPI1_MISO") (class "Default")
      (node (ref "MEM") (pin "SO") (pinfunction "SO_SO") (pintype "bidirectional"))
      (node (ref "TX/RX") (pin "9") (pinfunction "GPOI1_9") (pintype "bidirectional"))
      (node (ref "U1") (pin "25") (pinfunction "PA16(I2C/SER1:0+)_25") (pintype "bidirectional"))
    )
    (net (code "55") (name "SPI1_MOSI") (class "Default")
      (node (ref "MEM") (pin "SI") (pinfunction "SI_SI") (pintype "bidirectional"))
      (node (ref "TX/RX") (pin "7") (pinfunction "SI_7") (pintype "bidirectional"))
      (node (ref "U1") (pin "28") (pinfunction "PA19(SER1:3+)_28") (pintype "bidirectional"))
    )
    (net (code "56") (name "SPI1_SCK") (class "Default")
      (node (ref "MEM") (pin "SCK") (pinfunction "SCK_SCK") (pintype "bidirectional"))
      (node (ref "TX/RX") (pin "8") (pinfunction "SCLK_8") (pintype "bidirectional"))
      (node (ref "U1") (pin "26") (pinfunction "PA17(I2C/SER1:1+)_26") (pintype "bidirectional"))
    )
    (net (code "57") (name "SPI2_MISO") (class "Default")
      (node (ref "U$5") (pin "6") (pinfunction "SDO_6") (pintype "bidirectional"))
      (node (ref "U1") (pin "22") (pinfunction "PA13(I2C/SER2:1+)_22") (pintype "bidirectional"))
      (node (ref "U3") (pin "12") (pinfunction "SDO_12") (pintype "bidirectional"))
    )
    (net (code "58") (name "SPI2_MOSI") (class "Default")
      (node (ref "U$5") (pin "7") (pinfunction "SDI/SDA_7") (pintype "bidirectional"))
      (node (ref "U1") (pin "23") (pinfunction "PA14(XIN/SER2:2+)_23") (pintype "bidirectional"))
      (node (ref "U3") (pin "13") (pinfunction "SDA_13") (pintype "bidirectional"))
    )
    (net (code "59") (name "SPI2_SCK") (class "Default")
      (node (ref "U$5") (pin "8") (pinfunction "SCLK_8") (pintype "bidirectional"))
      (node (ref "U1") (pin "24") (pinfunction "PA15(XOUT/SER2:3+)_24") (pintype "bidirectional"))
      (node (ref "U3") (pin "14") (pinfunction "SCL_14") (pintype "bidirectional"))
    )
    (net (code "60") (name "SWCLK") (class "Default")
      (node (ref "JP1") (pin "4") (pinfunction "SWDCLK/TCK_4") (pintype "bidirectional"))
      (node (ref "U1") (pin "45") (pinfunction "PA30(SWCLK/SER1:2+)_45") (pintype "bidirectional"))
    )
    (net (code "61") (name "SWDIO") (class "Default")
      (node (ref "JP1") (pin "2") (pinfunction "SWDIO/TMS_2") (pintype "bidirectional"))
      (node (ref "U1") (pin "46") (pinfunction "PA31(SWDIO/SER1:3+)_46") (pintype "bidirectional"))
    )
    (net (code "62") (name "USB_D+") (class "Default")
      (node (ref "JP4") (pin "D+") (pinfunction "D+_D+") (pintype "bidirectional"))
      (node (ref "U1") (pin "34") (pinfunction "PA25(SER3:3+)_34") (pintype "bidirectional"))
    )
    (net (code "63") (name "USB_D-") (class "Default")
      (node (ref "JP4") (pin "D-") (pinfunction "D-_D-") (pintype "bidirectional"))
      (node (ref "U1") (pin "33") (pinfunction "PA24(SER3:2+)_33") (pintype "bidirectional"))
    )
    (net (code "64") (name "unconnected-(1U2-BP-Pad4)") (class "Default")
      (node (ref "1U2") (pin "4") (pinfunction "BP_4") (pintype "input"))
    )
    (net (code "65") (name "unconnected-(JP1-GNDDTCT-Pad9)") (class "Default")
      (node (ref "JP1") (pin "9") (pinfunction "GNDDTCT_9") (pintype "bidirectional"))
    )
    (net (code "66") (name "unconnected-(JP1-KEY-Pad7)") (class "Default")
      (node (ref "JP1") (pin "7") (pinfunction "KEY_7") (pintype "bidirectional"))
    )
    (net (code "67") (name "unconnected-(JP1-NC{slash}TDI-Pad8)") (class "Default")
      (node (ref "JP1") (pin "8") (pinfunction "NC/TDI_8") (pintype "bidirectional"))
    )
    (net (code "68") (name "unconnected-(JP1-SWO{slash}TDO-Pad6)") (class "Default")
      (node (ref "JP1") (pin "6") (pinfunction "SWO/TDO_6") (pintype "bidirectional"))
    )
    (net (code "69") (name "unconnected-(JP4-PadVBUS)") (class "Default")
      (node (ref "JP4") (pin "VBUS") (pinfunction "VBUS_VBUS") (pintype "bidirectional"))
    )
    (net (code "70") (name "unconnected-(TX/RX-GPIO0-Pad10)") (class "Default")
      (node (ref "TX/RX") (pin "10") (pinfunction "GPIO0_10") (pintype "bidirectional"))
    )
    (net (code "71") (name "unconnected-(TX/RX-GPIO2-Pad4)") (class "Default")
      (node (ref "TX/RX") (pin "4") (pinfunction "GPIO2_4") (pintype "bidirectional"))
    )
    (net (code "72") (name "unconnected-(TX/RX-GPIO3-Pad3)") (class "Default")
      (node (ref "TX/RX") (pin "3") (pinfunction "GPIO3_3") (pintype "bidirectional"))
    )
    (net (code "73") (name "unconnected-(TX/RX-N.C.-Pad16)") (class "Default")
      (node (ref "TX/RX") (pin "16") (pinfunction "N.C._16") (pintype "bidirectional"))
    )
    (net (code "74") (name "unconnected-(TX/RX-RESET_N-Pad2)") (class "Default")
      (node (ref "TX/RX") (pin "2") (pinfunction "RESET_N_2") (pintype "bidirectional"))
    )
    (net (code "75") (name "unconnected-(U$1-PadCLR)") (class "Default")
      (node (ref "U$1") (pin "CLR") (pinfunction "CLR_CLR") (pintype "bidirectional"))
    )
    (net (code "76") (name "unconnected-(U$1-~{OUT}-Pad!OUT)") (class "Default")
      (node (ref "U$1") (pin "!OUT") (pinfunction "~{OUT}_!OUT") (pintype "bidirectional"))
    )
    (net (code "77") (name "unconnected-(U$7-ST-PadP$4)") (class "Default")
      (node (ref "U$7") (pin "P$4") (pinfunction "ST_P$4") (pintype "bidirectional"))
    )
    (net (code "78") (name "unconnected-(U1-PA02(AIN0{slash}DAC)-Pad3)") (class "Default")
      (node (ref "U1") (pin "3") (pinfunction "PA02(AIN0/DAC)_3") (pintype "bidirectional"))
    )
    (net (code "79") (name "unconnected-(U1-PA03(AIN1{slash}REFA)-Pad4)") (class "Default")
      (node (ref "U1") (pin "4") (pinfunction "PA03(AIN1/REFA)_4") (pintype "bidirectional"))
    )
    (net (code "80") (name "unconnected-(U1-PA08(I2C{slash}AIN16{slash}SER0:0+)-Pad13)") (class "Default")
      (node (ref "U1") (pin "13") (pinfunction "PA08(I2C/AIN16/SER0:0+)_13") (pintype "bidirectional"))
    )
    (net (code "81") (name "unconnected-(U1-PA09(I2C{slash}AIN17{slash}SER0:1+)-Pad14)") (class "Default")
      (node (ref "U1") (pin "14") (pinfunction "PA09(I2C/AIN17/SER0:1+)_14") (pintype "bidirectional"))
    )
    (net (code "82") (name "unconnected-(U1-PA10(AIN18{slash}SER0:2+)-Pad15)") (class "Default")
      (node (ref "U1") (pin "15") (pinfunction "PA10(AIN18/SER0:2+)_15") (pintype "bidirectional"))
    )
    (net (code "83") (name "unconnected-(U1-PA11(AIN19{slash}SER0:3+)-Pad16)") (class "Default")
      (node (ref "U1") (pin "16") (pinfunction "PA11(AIN19/SER0:3+)_16") (pintype "bidirectional"))
    )
    (net (code "84") (name "unconnected-(U1-PA22(I2C{slash}SER3:0+)-Pad31)") (class "Default")
      (node (ref "U1") (pin "31") (pinfunction "PA22(I2C/SER3:0+)_31") (pintype "bidirectional"))
    )
    (net (code "85") (name "unconnected-(U1-PA23(I2C{slash}SER3:0+)-Pad32)") (class "Default")
      (node (ref "U1") (pin "32") (pinfunction "PA23(I2C/SER3:0+)_32") (pintype "bidirectional"))
    )
    (net (code "86") (name "unconnected-(U1-PA28-Pad41)") (class "Default")
      (node (ref "U1") (pin "41") (pinfunction "PA28_41") (pintype "bidirectional"))
    )
    (net (code "87") (name "unconnected-(U1-PB10(SER4:2+)-Pad19)") (class "Default")
      (node (ref "U1") (pin "19") (pinfunction "PB10(SER4:2+)_19") (pintype "bidirectional"))
    )
    (net (code "88") (name "unconnected-(U1-PB11(SER4:3+)-Pad20)") (class "Default")
      (node (ref "U1") (pin "20") (pinfunction "PB11(SER4:3+)_20") (pintype "bidirectional"))
    )
    (net (code "89") (name "unconnected-(U3-INT1-Pad8)") (class "Default")
      (node (ref "U3") (pin "8") (pinfunction "INT1_8") (pintype "bidirectional"))
    )
    (net (code "90") (name "unconnected-(U3-INT2-Pad9)") (class "Default")
      (node (ref "U3") (pin "9") (pinfunction "INT2_9") (pintype "bidirectional"))
    )
    (net (code "91") (name "unconnected-(U3-NC-Pad3)") (class "Default")
      (node (ref "U3") (pin "3") (pinfunction "NC_3") (pintype "bidirectional"))
    )
    (net (code "92") (name "unconnected-(U3-NC-Pad10)") (class "Default")
      (node (ref "U3") (pin "10") (pinfunction "NC_10") (pintype "bidirectional"))
    )
    (net (code "93") (name "unconnected-(U3-NC-Pad11)") (class "Default")
      (node (ref "U3") (pin "11") (pinfunction "NC_11") (pintype "bidirectional"))
    )
    (net (code "94") (name "unconnected-(U4-1PPS-PadP$13)") (class "Default")
      (node (ref "U4") (pin "P$13") (pinfunction "1PPS_P$13") (pintype "bidirectional"))
    )
    (net (code "95") (name "unconnected-(U4-EX_ANT-PadP$11)") (class "Default")
      (node (ref "U4") (pin "P$11") (pinfunction "EX_ANT_P$11") (pintype "bidirectional"))
    )
    (net (code "96") (name "unconnected-(U4-NC-PadP$6)") (class "Default")
      (node (ref "U4") (pin "P$6") (pinfunction "NC_P$6") (pintype "bidirectional"))
    )
    (net (code "97") (name "unconnected-(U4-NC-PadP$7)") (class "Default")
      (node (ref "U4") (pin "P$7") (pinfunction "NC_P$7") (pintype "bidirectional"))
    )
    (net (code "98") (name "unconnected-(U4-NC-PadP$15)") (class "Default")
      (node (ref "U4") (pin "P$15") (pinfunction "NC_P$15") (pintype "bidirectional"))
    )
    (net (code "99") (name "unconnected-(U4-NC-PadP$16)") (class "Default")
      (node (ref "U4") (pin "P$16") (pinfunction "NC_P$16") (pintype "bidirectional"))
    )
    (net (code "100") (name "unconnected-(U4-NC-PadP$17)") (class "Default")
      (node (ref "U4") (pin "P$17") (pinfunction "NC_P$17") (pintype "bidirectional"))
    )
    (net (code "101") (name "unconnected-(U4-NC-PadP$18)") (class "Default")
      (node (ref "U4") (pin "P$18") (pinfunction "NC_P$18") (pintype "bidirectional"))
    )
    (net (code "102") (name "unconnected-(U4-NC-PadP$20)") (class "Default")
      (node (ref "U4") (pin "P$20") (pinfunction "NC_P$20") (pintype "bidirectional"))
    )
    (net (code "103") (name "unconnected-(U4-NRESET-PadP$2)") (class "Default")
      (node (ref "U4") (pin "P$2") (pinfunction "NRESET_P$2") (pintype "bidirectional"))
    )
    (net (code "104") (name "unconnected-(U4-RTCM-PadP$14)") (class "Default")
      (node (ref "U4") (pin "P$14") (pinfunction "RTCM_P$14") (pintype "bidirectional"))
    )
    (net (code "105") (name "unconnected-(U4-VBACKUP-PadP$4)") (class "Default")
      (node (ref "U4") (pin "P$4") (pinfunction "VBACKUP_P$4") (pintype "bidirectional"))
    )
  )
)
